# 8_Outputs_Card_with_I2C.net
KiCad netlist of a schematic drawn in EasyEDA
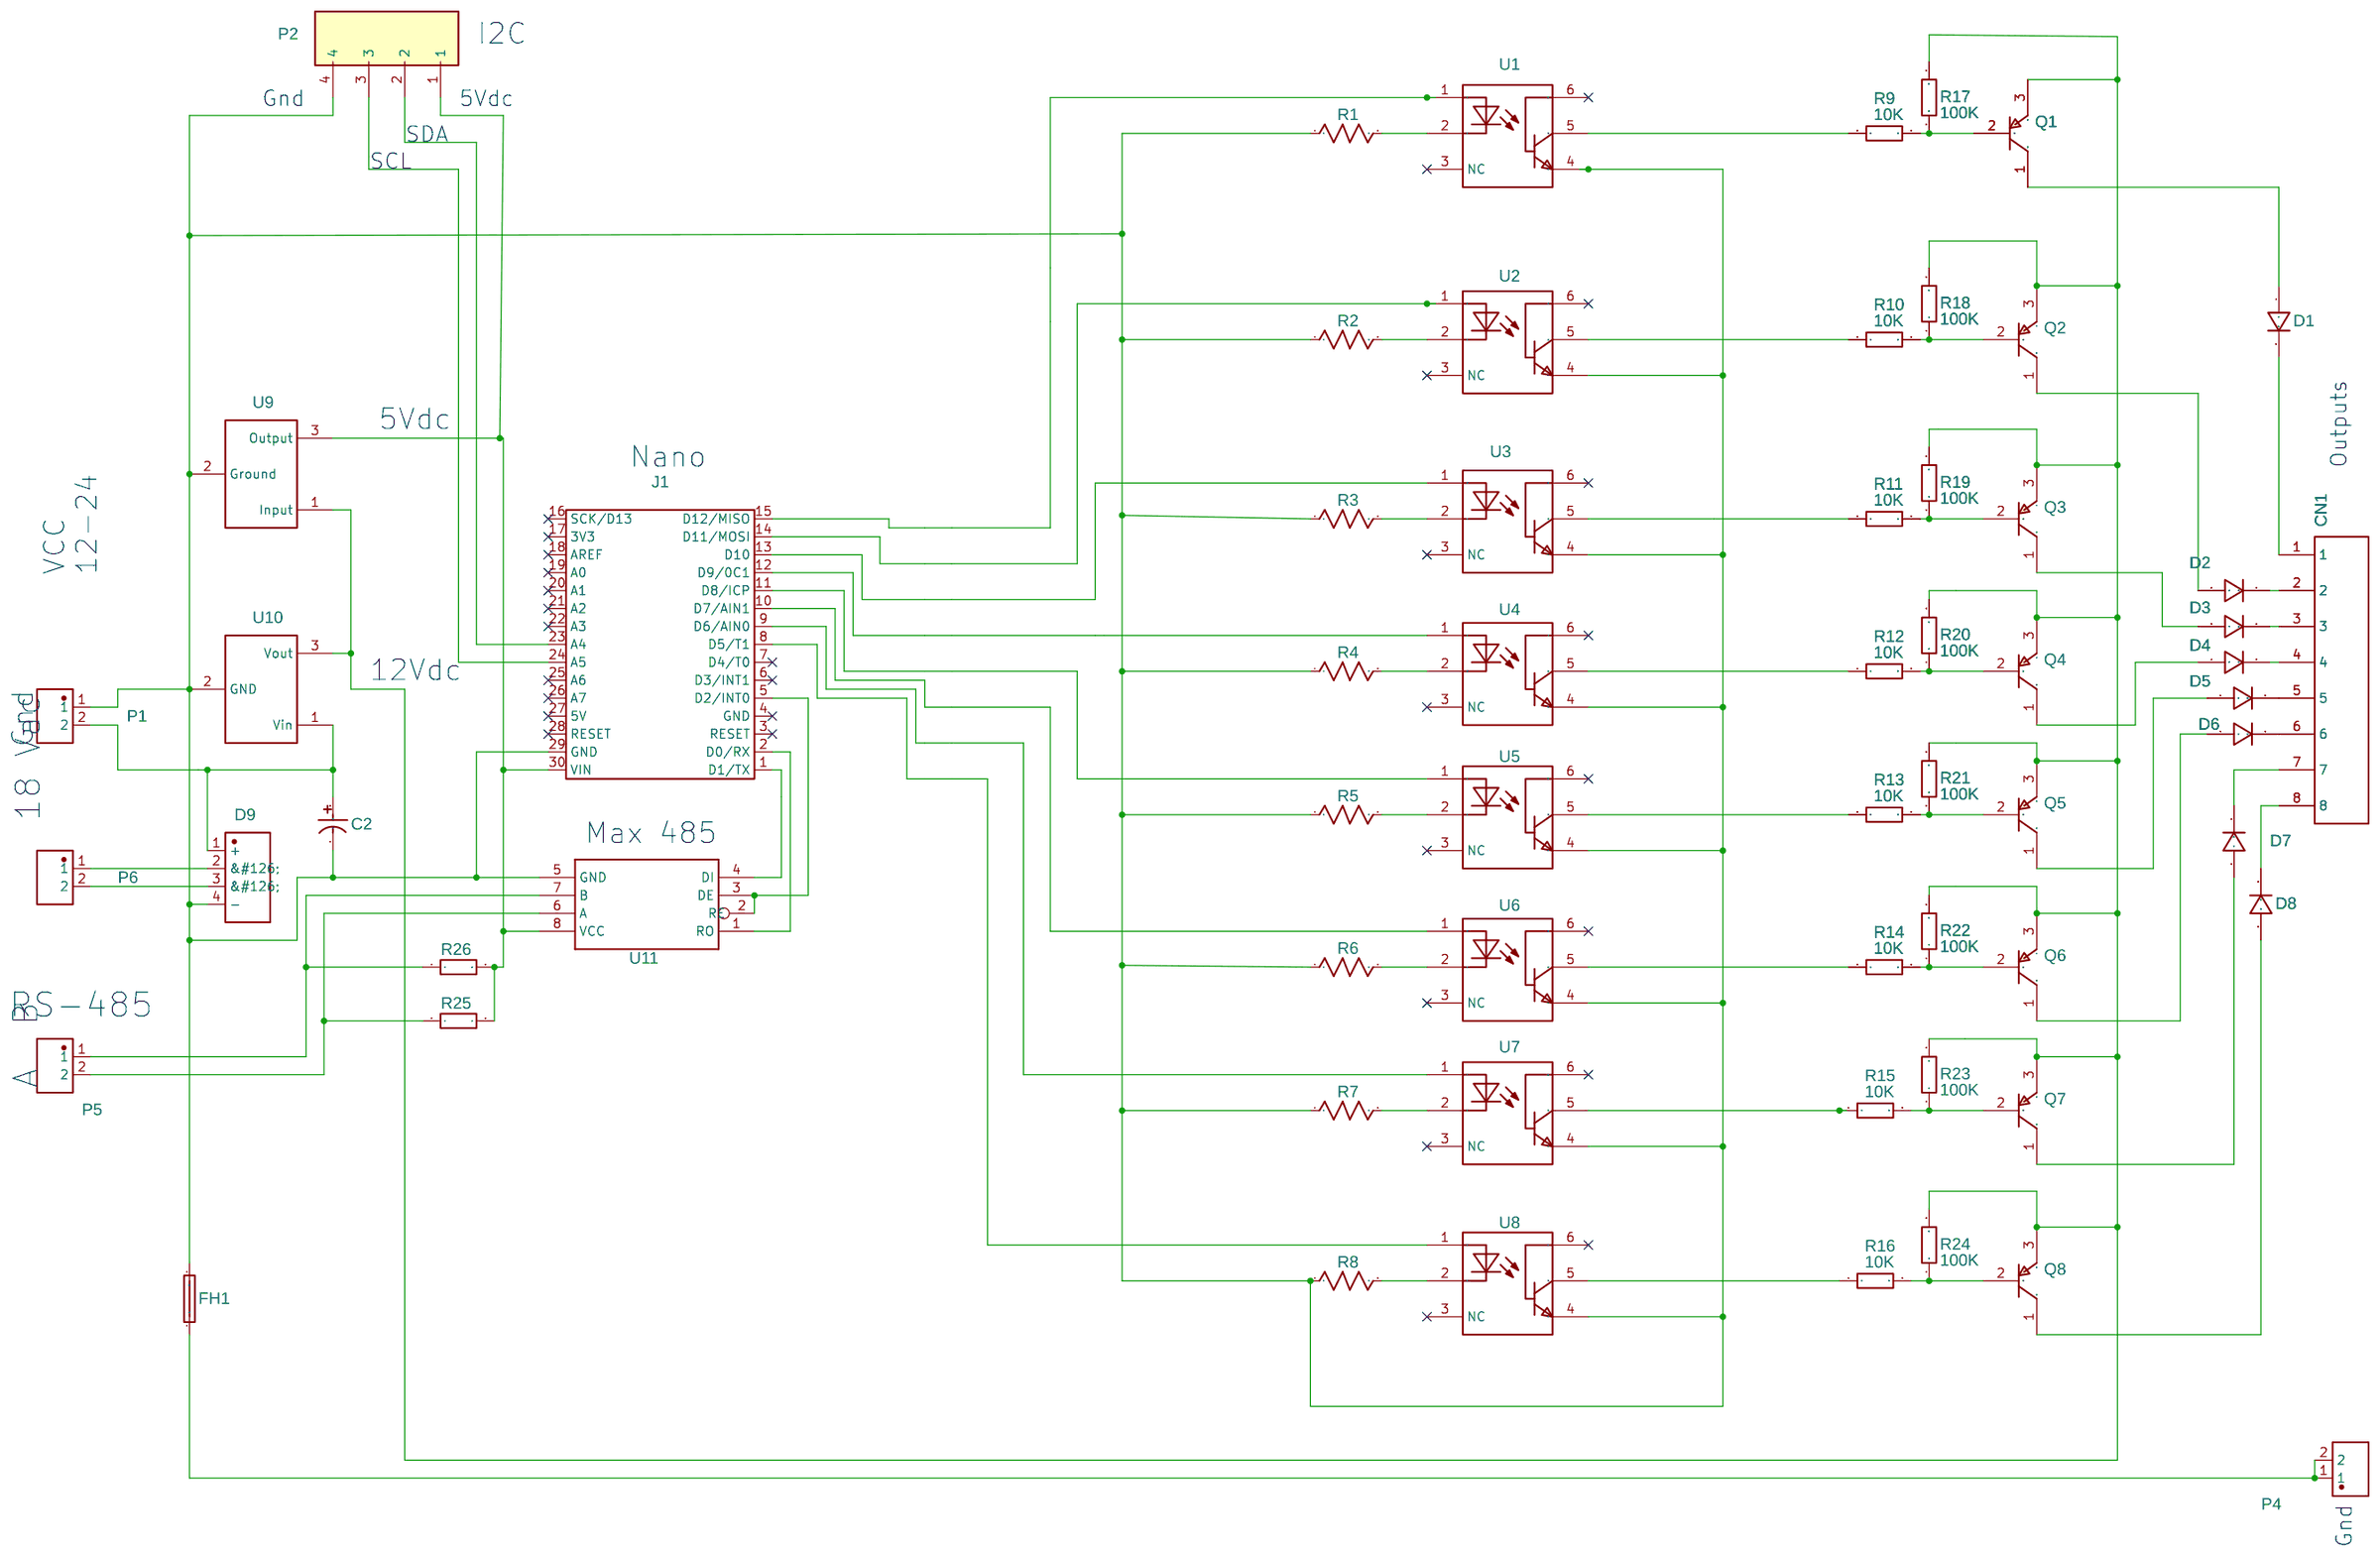
[diagram p0: schematic sheet]

(export (version "E")
  (design (tool "Eeschema 10.0.6"))
  (components
    (comp (ref "C2")
      (value "470uF")
      (fields
        (field (name "BOM_Manufacturer Part") "470uF 100V 16*25")
        (field (name "BOM_Supplier Part") "C72551")
      )
      (libsource (lib "") (part "470uF 100V 16*25"))
    )
    (comp (ref "CN1")
      (value "WJ25C-B-7.62-8P-13-00A")
      (fields (field (name "BOM_Supplier Part") "C49492"))
      (libsource (lib "") (part "Unknown_1530_395"))
    )
    (comp (ref "D1")
      (value "1N4001")
      (fields (field (name "BOM_Supplier Part") "C169150"))
      (libsource (lib "") (part "Unknown_1510_195"))
    )
    (comp (ref "D2")
      (value "1N4001")
      (fields (field (name "BOM_Supplier Part") "C169150"))
      (libsource (lib "") (part "Unknown_1485_345"))
    )
    (comp (ref "D3")
      (value "1N4001")
      (fields (field (name "BOM_Supplier Part") "C169150"))
      (libsource (lib "") (part "Unknown_1485_365"))
    )
    (comp (ref "D4")
      (value "1N4001")
      (fields (field (name "BOM_Supplier Part") "C169150"))
      (libsource (lib "") (part "Unknown_1485_385"))
    )
    (comp (ref "D5")
      (value "1N4001")
      (fields (field (name "BOM_Supplier Part") "C169150"))
      (libsource (lib "") (part "Unknown_1490_405"))
    )
    (comp (ref "D6")
      (value "1N4001")
      (fields (field (name "BOM_Supplier Part") "C169150"))
      (libsource (lib "") (part "Unknown_1490_425"))
    )
    (comp (ref "D7")
      (value "1N4001")
      (fields (field (name "BOM_Supplier Part") "C169150"))
      (libsource (lib "") (part "Unknown_1485_485"))
    )
    (comp (ref "D8")
      (value "1N4001")
      (fields (field (name "BOM_Supplier Part") "C169150"))
      (libsource (lib "") (part "Unknown_1500_520"))
    )
    (comp (ref "D9")
      (value "D50SB100")
      (fields (field (name "BOM_Supplier Part") "C411148"))
      (libsource (lib "") (part "Unknown_370_505"))
    )
    (comp (ref "FH1")
      (value "64600001003")
      (fields (field (name "BOM_Supplier Part") "C206887"))
      (libsource (lib "") (part "Unknown_345_740"))
    )
    (comp (ref "J1") (value "Arduino_Nano_Header") (libsource (lib "") (part "Unknown_605_375")))
    (comp (ref "P1")
      (value "WJ25C-B-2P")
      (fields (field (name "BOM_Supplier Part") "C8422"))
      (libsource (lib "") (part "Unknown_270_415"))
    )
    (comp (ref "P2")
      (value "WJ25C-B-4P")
      (fields (field (name "BOM_Supplier Part") "C8424"))
      (libsource (lib "") (part "WJ25C-B-4P"))
    )
    (comp (ref "P4")
      (value "WJ25C-B-2P")
      (fields (field (name "BOM_Supplier Part") "C8422"))
      (libsource (lib "") (part "Unknown_1550_835"))
    )
    (comp (ref "P5")
      (value "WJ25C-B-2P")
      (fields (field (name "BOM_Supplier Part") "C8422"))
      (libsource (lib "") (part "Unknown_270_610"))
    )
    (comp (ref "P6")
      (value "WJ25C-B-2P")
      (fields (field (name "BOM_Supplier Part") "C8422"))
      (libsource (lib "") (part "Unknown_270_505"))
    )
    (comp (ref "Q1")
      (value "2N4033")
      (fields (field (name "BOM_Supplier Part") "610-2N4033"))
      (libsource (lib "") (part "Unknown_1355_90"))
    )
    (comp (ref "Q2")
      (value "2N4033")
      (fields (field (name "BOM_Supplier Part") "610-2N4033"))
      (libsource (lib "") (part "Unknown_1360_205"))
    )
    (comp (ref "Q3")
      (value "2N4033")
      (fields (field (name "BOM_Supplier Part") "610-2N4033"))
      (libsource (lib "") (part "Unknown_1360_305"))
    )
    (comp (ref "Q4")
      (value "2N4033")
      (fields (field (name "BOM_Supplier Part") "610-2N4033"))
      (libsource (lib "") (part "Unknown_1360_390"))
    )
    (comp (ref "Q5")
      (value "2N4033")
      (fields (field (name "BOM_Supplier Part") "610-2N4033"))
      (libsource (lib "") (part "Unknown_1360_470"))
    )
    (comp (ref "Q6")
      (value "2N4033")
      (fields (field (name "BOM_Supplier Part") "610-2N4033"))
      (libsource (lib "") (part "Unknown_1360_555"))
    )
    (comp (ref "Q7")
      (value "2N4033")
      (fields (field (name "BOM_Supplier Part") "610-2N4033"))
      (libsource (lib "") (part "Unknown_1360_635"))
    )
    (comp (ref "Q8")
      (value "2N4033")
      (fields (field (name "BOM_Supplier Part") "610-2N4033"))
      (libsource (lib "") (part "Unknown_1360_730"))
    )
    (comp (ref "R1")
      (value "1k")
      (fields
        (field (name "BOM_Manufacturer Part") "MFR0W4F1001A50")
        (field (name "BOM_Supplier Part") "C57435")
      )
      (libsource (lib "") (part "Res_AXIAL-0.3(1/8W)_US"))
    )
    (comp (ref "R2")
      (value "1k")
      (fields
        (field (name "BOM_Manufacturer Part") "MFR0W4F1001A50")
        (field (name "BOM_Supplier Part") "C57435")
      )
      (libsource (lib "") (part "Res_AXIAL-0.3(1/8W)_US"))
    )
    (comp (ref "R3")
      (value "1k")
      (fields
        (field (name "BOM_Manufacturer Part") "MFR0W4F1001A50")
        (field (name "BOM_Supplier Part") "C57435")
      )
      (libsource (lib "") (part "Res_AXIAL-0.3(1/8W)_US"))
    )
    (comp (ref "R4")
      (value "1k")
      (fields
        (field (name "BOM_Manufacturer Part") "MFR0W4F1001A50")
        (field (name "BOM_Supplier Part") "C57435")
      )
      (libsource (lib "") (part "Res_AXIAL-0.3(1/8W)_US"))
    )
    (comp (ref "R5")
      (value "1k")
      (fields
        (field (name "BOM_Manufacturer Part") "MFR0W4F1001A50")
        (field (name "BOM_Supplier Part") "C57435")
      )
      (libsource (lib "") (part "Res_AXIAL-0.3(1/8W)_US"))
    )
    (comp (ref "R6")
      (value "1k")
      (fields
        (field (name "BOM_Manufacturer Part") "MFR0W4F1001A50")
        (field (name "BOM_Supplier Part") "C57435")
      )
      (libsource (lib "") (part "Res_AXIAL-0.3(1/8W)_US"))
    )
    (comp (ref "R7")
      (value "1k")
      (fields
        (field (name "BOM_Manufacturer Part") "MFR0W4F1001A50")
        (field (name "BOM_Supplier Part") "C57435")
      )
      (libsource (lib "") (part "Res_AXIAL-0.3(1/8W)_US"))
    )
    (comp (ref "R8")
      (value "1k")
      (fields
        (field (name "BOM_Manufacturer Part") "MFR0W4F1001A50")
        (field (name "BOM_Supplier Part") "C57435")
      )
      (libsource (lib "") (part "Res_AXIAL-0.3(1/8W)_US"))
    )
    (comp (ref "R9")
      (value "10K")
      (fields
        (field (name "BOM_Manufacturer Part") "CFR0W4J0103A50")
        (field (name "BOM_Supplier Part") "C61299")
      )
      (libsource (lib "") (part "CFR0W4J0103A50"))
    )
    (comp (ref "R10")
      (value "10K")
      (fields
        (field (name "BOM_Manufacturer Part") "CFR0W4J0103A50")
        (field (name "BOM_Supplier Part") "C61299")
      )
      (libsource (lib "") (part "CFR0W4J0103A50"))
    )
    (comp (ref "R11")
      (value "10K")
      (fields
        (field (name "BOM_Manufacturer Part") "CFR0W4J0103A50")
        (field (name "BOM_Supplier Part") "C61299")
      )
      (libsource (lib "") (part "CFR0W4J0103A50"))
    )
    (comp (ref "R12")
      (value "10K")
      (fields
        (field (name "BOM_Manufacturer Part") "CFR0W4J0103A50")
        (field (name "BOM_Supplier Part") "C61299")
      )
      (libsource (lib "") (part "CFR0W4J0103A50"))
    )
    (comp (ref "R13")
      (value "10K")
      (fields
        (field (name "BOM_Manufacturer Part") "CFR0W4J0103A50")
        (field (name "BOM_Supplier Part") "C61299")
      )
      (libsource (lib "") (part "CFR0W4J0103A50"))
    )
    (comp (ref "R14")
      (value "10K")
      (fields
        (field (name "BOM_Manufacturer Part") "CFR0W4J0103A50")
        (field (name "BOM_Supplier Part") "C61299")
      )
      (libsource (lib "") (part "CFR0W4J0103A50"))
    )
    (comp (ref "R15")
      (value "10K")
      (fields
        (field (name "BOM_Manufacturer Part") "CFR0W4J0103A50")
        (field (name "BOM_Supplier Part") "C61299")
      )
      (libsource (lib "") (part "CFR0W4J0103A50"))
    )
    (comp (ref "R16")
      (value "10K")
      (fields
        (field (name "BOM_Manufacturer Part") "CFR0W4J0103A50")
        (field (name "BOM_Supplier Part") "C61299")
      )
      (libsource (lib "") (part "CFR0W4J0103A50"))
    )
    (comp (ref "R17")
      (value "100K")
      (fields
        (field (name "BOM_Manufacturer Part") "CFR0W4J0104A50")
        (field (name "BOM_Supplier Part") "C61303")
      )
      (libsource (lib "") (part "CFR0W4J0104A50"))
    )
    (comp (ref "R18")
      (value "100K")
      (fields
        (field (name "BOM_Manufacturer Part") "CFR0W4J0104A50")
        (field (name "BOM_Supplier Part") "C61303")
      )
      (libsource (lib "") (part "CFR0W4J0104A50"))
    )
    (comp (ref "R19")
      (value "100K")
      (fields
        (field (name "BOM_Manufacturer Part") "CFR0W4J0104A50")
        (field (name "BOM_Supplier Part") "C61303")
      )
      (libsource (lib "") (part "CFR0W4J0104A50"))
    )
    (comp (ref "R20")
      (value "100K")
      (fields
        (field (name "BOM_Manufacturer Part") "CFR0W4J0104A50")
        (field (name "BOM_Supplier Part") "C61303")
      )
      (libsource (lib "") (part "CFR0W4J0104A50"))
    )
    (comp (ref "R21")
      (value "100K")
      (fields
        (field (name "BOM_Manufacturer Part") "CFR0W4J0104A50")
        (field (name "BOM_Supplier Part") "C61303")
      )
      (libsource (lib "") (part "CFR0W4J0104A50"))
    )
    (comp (ref "R22")
      (value "100K")
      (fields
        (field (name "BOM_Manufacturer Part") "CFR0W4J0104A50")
        (field (name "BOM_Supplier Part") "C61303")
      )
      (libsource (lib "") (part "CFR0W4J0104A50"))
    )
    (comp (ref "R23")
      (value "100K")
      (fields
        (field (name "BOM_Manufacturer Part") "CFR0W4J0104A50")
        (field (name "BOM_Supplier Part") "C61303")
      )
      (libsource (lib "") (part "CFR0W4J0104A50"))
    )
    (comp (ref "R24")
      (value "100K")
      (fields
        (field (name "BOM_Manufacturer Part") "CFR0W4J0104A50")
        (field (name "BOM_Supplier Part") "C61303")
      )
      (libsource (lib "") (part "CFR0W4J0104A50"))
    )
    (comp (ref "R25")
      (value "10K")
      (fields
        (field (name "BOM_Manufacturer Part") "CFR0W4J0103A50")
        (field (name "BOM_Supplier Part") "C61299")
      )
      (libsource (lib "") (part "CFR0W4J0103A50"))
    )
    (comp (ref "R26")
      (value "10K")
      (fields
        (field (name "BOM_Manufacturer Part") "CFR0W4J0103A50")
        (field (name "BOM_Supplier Part") "C61299")
      )
      (libsource (lib "") (part "CFR0W4J0103A50"))
    )
    (comp (ref "U1")
      (value "4N25M")
      (fields (field (name "BOM_Supplier Part") "C5241"))
      (libsource (lib "") (part "Unknown_1080_90"))
    )
    (comp (ref "U2")
      (value "4N25M")
      (fields (field (name "BOM_Supplier Part") "C5241"))
      (libsource (lib "") (part "Unknown_1080_205"))
    )
    (comp (ref "U3")
      (value "4N25M")
      (fields (field (name "BOM_Supplier Part") "C5241"))
      (libsource (lib "") (part "Unknown_1080_305"))
    )
    (comp (ref "U4")
      (value "4N25M")
      (fields (field (name "BOM_Supplier Part") "C5241"))
      (libsource (lib "") (part "Unknown_1080_390"))
    )
    (comp (ref "U5")
      (value "4N25M")
      (fields (field (name "BOM_Supplier Part") "C5241"))
      (libsource (lib "") (part "Unknown_1080_470"))
    )
    (comp (ref "U6")
      (value "4N25M")
      (fields (field (name "BOM_Supplier Part") "C5241"))
      (libsource (lib "") (part "Unknown_1080_555"))
    )
    (comp (ref "U7")
      (value "4N25M")
      (fields (field (name "BOM_Supplier Part") "C5241"))
      (libsource (lib "") (part "Unknown_1080_635"))
    )
    (comp (ref "U8")
      (value "4N25M")
      (fields (field (name "BOM_Supplier Part") "C5241"))
      (libsource (lib "") (part "Unknown_1080_730"))
    )
    (comp (ref "U9")
      (value "MC7805BTG")
      (fields (field (name "BOM_Supplier Part") "C45385"))
      (libsource (lib "") (part "Unknown_385_280"))
    )
    (comp (ref "U10")
      (value "CJ7812")
      (fields (field (name "BOM_Supplier Part") "C77894"))
      (libsource (lib "") (part "Unknown_385_400"))
    )
    (comp (ref "U11") (value "MAX485DIL") (libsource (lib "") (part "Unknown_600_520")))
  )
  (nets
    (net (code "1") (name "Net-(CN1-Pad1)") (class "Default")
      (node (ref "CN1") (pin "1") (pinfunction "1_1") (pintype "input"))
      (node (ref "D1") (pin "2") (pinfunction "2_2") (pintype "unspecified"))
    )
    (net (code "2") (name "Net-(CN1-Pad2)") (class "Default")
      (node (ref "CN1") (pin "2") (pinfunction "2_2") (pintype "input"))
      (node (ref "D2") (pin "2") (pinfunction "2_2") (pintype "unspecified"))
    )
    (net (code "3") (name "Net-(CN1-Pad3)") (class "Default")
      (node (ref "CN1") (pin "3") (pinfunction "3_3") (pintype "input"))
      (node (ref "D3") (pin "2") (pinfunction "2_2") (pintype "unspecified"))
    )
    (net (code "4") (name "Net-(CN1-Pad4)") (class "Default")
      (node (ref "CN1") (pin "4") (pinfunction "4_4") (pintype "input"))
      (node (ref "D4") (pin "2") (pinfunction "2_2") (pintype "unspecified"))
    )
    (net (code "5") (name "Net-(CN1-Pad5)") (class "Default")
      (node (ref "CN1") (pin "5") (pinfunction "5_5") (pintype "input"))
      (node (ref "D5") (pin "2") (pinfunction "2_2") (pintype "unspecified"))
    )
    (net (code "6") (name "Net-(CN1-Pad6)") (class "Default")
      (node (ref "CN1") (pin "6") (pinfunction "6_6") (pintype "input"))
      (node (ref "D6") (pin "2") (pinfunction "2_2") (pintype "unspecified"))
    )
    (net (code "7") (name "Net-(CN1-Pad7)") (class "Default")
      (node (ref "CN1") (pin "7") (pinfunction "7_7") (pintype "input"))
      (node (ref "D7") (pin "2") (pinfunction "2_2") (pintype "unspecified"))
    )
    (net (code "8") (name "Net-(CN1-Pad8)") (class "Default")
      (node (ref "CN1") (pin "8") (pinfunction "8_8") (pintype "input"))
      (node (ref "D8") (pin "2") (pinfunction "2_2") (pintype "unspecified"))
    )
    (net (code "9") (name "Net-(D9-&#126;-Pad2)") (class "Default")
      (node (ref "D9") (pin "2") (pinfunction "&#126;_2") (pintype "unspecified"))
      (node (ref "P6") (pin "1") (pinfunction "1_1") (pintype "unspecified"))
    )
    (net (code "10") (name "Net-(D9-&#126;-Pad3)") (class "Default")
      (node (ref "D9") (pin "3") (pinfunction "&#126;_3") (pintype "unspecified"))
      (node (ref "P6") (pin "2") (pinfunction "2_2") (pintype "unspecified"))
    )
    (net (code "11") (name "Net-(D9-+)") (class "Default")
      (node (ref "C2") (pin "1") (pinfunction "1_1") (pintype "input"))
      (node (ref "D9") (pin "1") (pinfunction "+_1") (pintype "unspecified"))
      (node (ref "P1") (pin "2") (pinfunction "2_2") (pintype "unspecified"))
      (node (ref "U10") (pin "1") (pinfunction "Vin_1") (pintype "unspecified"))
    )
    (net (code "12") (name "Net-(D9--)") (class "Default")
      (node (ref "C2") (pin "2") (pinfunction "2_2") (pintype "input"))
      (node (ref "D9") (pin "4") (pinfunction "-_4") (pintype "unspecified"))
      (node (ref "FH1") (pin "2") (pinfunction "2_2") (pintype "unspecified"))
      (node (ref "J1") (pin "29") (pinfunction "GND_29") (pintype "unspecified"))
      (node (ref "P1") (pin "1") (pinfunction "1_1") (pintype "unspecified"))
      (node (ref "P2") (pin "4") (pinfunction "4_4") (pintype "input"))
      (node (ref "R1") (pin "1") (pinfunction "1_1") (pintype "unspecified"))
      (node (ref "R2") (pin "1") (pinfunction "1_1") (pintype "unspecified"))
      (node (ref "R3") (pin "1") (pinfunction "1_1") (pintype "unspecified"))
      (node (ref "R4") (pin "1") (pinfunction "1_1") (pintype "unspecified"))
      (node (ref "R5") (pin "1") (pinfunction "1_1") (pintype "unspecified"))
      (node (ref "R6") (pin "1") (pinfunction "1_1") (pintype "unspecified"))
      (node (ref "R7") (pin "1") (pinfunction "1_1") (pintype "unspecified"))
      (node (ref "R8") (pin "1") (pinfunction "1_1") (pintype "unspecified"))
      (node (ref "U1") (pin "4") (pinfunction "4_4") (pintype "unspecified"))
      (node (ref "U10") (pin "2") (pinfunction "GND_2") (pintype "unspecified"))
      (node (ref "U11") (pin "5") (pinfunction "GND_5") (pintype "unspecified"))
      (node (ref "U2") (pin "4") (pinfunction "4_4") (pintype "unspecified"))
      (node (ref "U3") (pin "4") (pinfunction "4_4") (pintype "unspecified"))
      (node (ref "U4") (pin "4") (pinfunction "4_4") (pintype "unspecified"))
      (node (ref "U5") (pin "4") (pinfunction "4_4") (pintype "unspecified"))
      (node (ref "U6") (pin "4") (pinfunction "4_4") (pintype "unspecified"))
      (node (ref "U7") (pin "4") (pinfunction "4_4") (pintype "unspecified"))
      (node (ref "U8") (pin "4") (pinfunction "4_4") (pintype "unspecified"))
      (node (ref "U9") (pin "2") (pinfunction "Ground_2") (pintype "unspecified"))
    )
    (net (code "13") (name "Net-(FH1-Pad1)") (class "Default")
      (node (ref "FH1") (pin "1") (pinfunction "1_1") (pintype "unspecified"))
      (node (ref "P4") (pin "1") (pinfunction "1_1") (pintype "unspecified"))
      (node (ref "P4") (pin "2") (pinfunction "2_2") (pintype "unspecified"))
    )
    (net (code "14") (name "Net-(J1-A4)") (class "Default")
      (node (ref "J1") (pin "23") (pinfunction "A4_23") (pintype "unspecified"))
      (node (ref "P2") (pin "2") (pinfunction "2_2") (pintype "input"))
    )
    (net (code "15") (name "Net-(J1-A5)") (class "Default")
      (node (ref "J1") (pin "24") (pinfunction "A5_24") (pintype "unspecified"))
      (node (ref "P2") (pin "3") (pinfunction "3_3") (pintype "input"))
    )
    (net (code "16") (name "Net-(J1-D0{slash}RX)") (class "Default")
      (node (ref "J1") (pin "2") (pinfunction "D0/RX_2") (pintype "unspecified"))
      (node (ref "U11") (pin "1") (pinfunction "RO_1") (pintype "unspecified"))
    )
    (net (code "17") (name "Net-(J1-D1{slash}TX)") (class "Default")
      (node (ref "J1") (pin "1") (pinfunction "D1/TX_1") (pintype "unspecified"))
      (node (ref "U11") (pin "4") (pinfunction "DI_4") (pintype "unspecified"))
    )
    (net (code "18") (name "Net-(J1-D2{slash}INT0)") (class "Default")
      (node (ref "J1") (pin "5") (pinfunction "D2/INT0_5") (pintype "unspecified"))
      (node (ref "U11") (pin "2") (pinfunction "RE_2") (pintype "unspecified"))
      (node (ref "U11") (pin "3") (pinfunction "DE_3") (pintype "unspecified"))
    )
    (net (code "19") (name "Net-(J1-D5{slash}T1)") (class "Default")
      (node (ref "J1") (pin "8") (pinfunction "D5/T1_8") (pintype "unspecified"))
      (node (ref "U8") (pin "1") (pinfunction "1_1") (pintype "unspecified"))
    )
    (net (code "20") (name "Net-(J1-D6{slash}AIN0)") (class "Default")
      (node (ref "J1") (pin "9") (pinfunction "D6/AIN0_9") (pintype "unspecified"))
      (node (ref "U7") (pin "1") (pinfunction "1_1") (pintype "unspecified"))
    )
    (net (code "21") (name "Net-(J1-D7{slash}AIN1)") (class "Default")
      (node (ref "J1") (pin "10") (pinfunction "D7/AIN1_10") (pintype "unspecified"))
      (node (ref "U6") (pin "1") (pinfunction "1_1") (pintype "unspecified"))
    )
    (net (code "22") (name "Net-(J1-D8{slash}ICP)") (class "Default")
      (node (ref "J1") (pin "11") (pinfunction "D8/ICP_11") (pintype "unspecified"))
      (node (ref "U5") (pin "1") (pinfunction "1_1") (pintype "unspecified"))
    )
    (net (code "23") (name "Net-(J1-D9{slash}0C1)") (class "Default")
      (node (ref "J1") (pin "12") (pinfunction "D9/0C1_12") (pintype "unspecified"))
      (node (ref "U4") (pin "1") (pinfunction "1_1") (pintype "unspecified"))
    )
    (net (code "24") (name "Net-(J1-D10)") (class "Default")
      (node (ref "J1") (pin "13") (pinfunction "D10_13") (pintype "unspecified"))
      (node (ref "U3") (pin "1") (pinfunction "1_1") (pintype "unspecified"))
    )
    (net (code "25") (name "Net-(J1-D11{slash}MOSI)") (class "Default")
      (node (ref "J1") (pin "14") (pinfunction "D11/MOSI_14") (pintype "unspecified"))
      (node (ref "U2") (pin "1") (pinfunction "1_1") (pintype "unspecified"))
    )
    (net (code "26") (name "Net-(J1-D12{slash}MISO)") (class "Default")
      (node (ref "J1") (pin "15") (pinfunction "D12/MISO_15") (pintype "unspecified"))
      (node (ref "U1") (pin "1") (pinfunction "1_1") (pintype "unspecified"))
    )
    (net (code "27") (name "Net-(J1-VIN)") (class "Default")
      (node (ref "J1") (pin "30") (pinfunction "VIN_30") (pintype "unspecified"))
      (node (ref "P2") (pin "1") (pinfunction "1_1") (pintype "input"))
      (node (ref "R25") (pin "2") (pinfunction "2_2") (pintype "input"))
      (node (ref "R26") (pin "2") (pinfunction "2_2") (pintype "input"))
      (node (ref "U11") (pin "8") (pinfunction "VCC_8") (pintype "unspecified"))
      (node (ref "U9") (pin "3") (pinfunction "Output_3") (pintype "unspecified"))
    )
    (net (code "28") (name "Net-(Q1-B)") (class "Default")
      (node (ref "Q1") (pin "2") (pinfunction "B_2") (pintype "unspecified"))
      (node (ref "R17") (pin "1") (pinfunction "1_1") (pintype "input"))
      (node (ref "R9") (pin "2") (pinfunction "2_2") (pintype "input"))
    )
    (net (code "29") (name "Net-(Q1-C)") (class "Default")
      (node (ref "D1") (pin "1") (pinfunction "1_1") (pintype "unspecified"))
      (node (ref "Q1") (pin "1") (pinfunction "C_1") (pintype "unspecified"))
    )
    (net (code "30") (name "Net-(Q1-E)") (class "Default")
      (node (ref "Q1") (pin "3") (pinfunction "E_3") (pintype "unspecified"))
      (node (ref "Q2") (pin "3") (pinfunction "E_3") (pintype "unspecified"))
      (node (ref "Q3") (pin "3") (pinfunction "E_3") (pintype "unspecified"))
      (node (ref "Q4") (pin "3") (pinfunction "E_3") (pintype "unspecified"))
      (node (ref "Q5") (pin "3") (pinfunction "E_3") (pintype "unspecified"))
      (node (ref "Q6") (pin "3") (pinfunction "E_3") (pintype "unspecified"))
      (node (ref "Q7") (pin "3") (pinfunction "E_3") (pintype "unspecified"))
      (node (ref "Q8") (pin "3") (pinfunction "E_3") (pintype "unspecified"))
      (node (ref "R17") (pin "2") (pinfunction "2_2") (pintype "input"))
      (node (ref "R18") (pin "2") (pinfunction "2_2") (pintype "input"))
      (node (ref "R19") (pin "2") (pinfunction "2_2") (pintype "input"))
      (node (ref "R20") (pin "2") (pinfunction "2_2") (pintype "input"))
      (node (ref "R21") (pin "2") (pinfunction "2_2") (pintype "input"))
      (node (ref "R22") (pin "2") (pinfunction "2_2") (pintype "input"))
      (node (ref "R23") (pin "2") (pinfunction "2_2") (pintype "input"))
      (node (ref "R24") (pin "2") (pinfunction "2_2") (pintype "input"))
      (node (ref "U10") (pin "3") (pinfunction "Vout_3") (pintype "unspecified"))
      (node (ref "U9") (pin "1") (pinfunction "Input_1") (pintype "unspecified"))
    )
    (net (code "31") (name "Net-(Q2-B)") (class "Default")
      (node (ref "Q2") (pin "2") (pinfunction "B_2") (pintype "unspecified"))
      (node (ref "R10") (pin "2") (pinfunction "2_2") (pintype "input"))
      (node (ref "R18") (pin "1") (pinfunction "1_1") (pintype "input"))
    )
    (net (code "32") (name "Net-(Q2-C)") (class "Default")
      (node (ref "D2") (pin "1") (pinfunction "1_1") (pintype "unspecified"))
      (node (ref "Q2") (pin "1") (pinfunction "C_1") (pintype "unspecified"))
    )
    (net (code "33") (name "Net-(Q3-B)") (class "Default")
      (node (ref "Q3") (pin "2") (pinfunction "B_2") (pintype "unspecified"))
      (node (ref "R11") (pin "2") (pinfunction "2_2") (pintype "input"))
      (node (ref "R19") (pin "1") (pinfunction "1_1") (pintype "input"))
    )
    (net (code "34") (name "Net-(Q3-C)") (class "Default")
      (node (ref "D3") (pin "1") (pinfunction "1_1") (pintype "unspecified"))
      (node (ref "Q3") (pin "1") (pinfunction "C_1") (pintype "unspecified"))
    )
    (net (code "35") (name "Net-(Q4-B)") (class "Default")
      (node (ref "Q4") (pin "2") (pinfunction "B_2") (pintype "unspecified"))
      (node (ref "R12") (pin "2") (pinfunction "2_2") (pintype "input"))
      (node (ref "R20") (pin "1") (pinfunction "1_1") (pintype "input"))
    )
    (net (code "36") (name "Net-(Q4-C)") (class "Default")
      (node (ref "D4") (pin "1") (pinfunction "1_1") (pintype "unspecified"))
      (node (ref "Q4") (pin "1") (pinfunction "C_1") (pintype "unspecified"))
    )
    (net (code "37") (name "Net-(Q5-B)") (class "Default")
      (node (ref "Q5") (pin "2") (pinfunction "B_2") (pintype "unspecified"))
      (node (ref "R13") (pin "2") (pinfunction "2_2") (pintype "input"))
      (node (ref "R21") (pin "1") (pinfunction "1_1") (pintype "input"))
    )
    (net (code "38") (name "Net-(Q5-C)") (class "Default")
      (node (ref "D5") (pin "1") (pinfunction "1_1") (pintype "unspecified"))
      (node (ref "Q5") (pin "1") (pinfunction "C_1") (pintype "unspecified"))
    )
    (net (code "39") (name "Net-(Q6-B)") (class "Default")
      (node (ref "Q6") (pin "2") (pinfunction "B_2") (pintype "unspecified"))
      (node (ref "R14") (pin "2") (pinfunction "2_2") (pintype "input"))
      (node (ref "R22") (pin "1") (pinfunction "1_1") (pintype "input"))
    )
    (net (code "40") (name "Net-(Q6-C)") (class "Default")
      (node (ref "D6") (pin "1") (pinfunction "1_1") (pintype "unspecified"))
      (node (ref "Q6") (pin "1") (pinfunction "C_1") (pintype "unspecified"))
    )
    (net (code "41") (name "Net-(Q7-B)") (class "Default")
      (node (ref "Q7") (pin "2") (pinfunction "B_2") (pintype "unspecified"))
      (node (ref "R15") (pin "2") (pinfunction "2_2") (pintype "input"))
      (node (ref "R23") (pin "1") (pinfunction "1_1") (pintype "input"))
    )
    (net (code "42") (name "Net-(Q7-C)") (class "Default")
      (node (ref "D7") (pin "1") (pinfunction "1_1") (pintype "unspecified"))
      (node (ref "Q7") (pin "1") (pinfunction "C_1") (pintype "unspecified"))
    )
    (net (code "43") (name "Net-(Q8-B)") (class "Default")
      (node (ref "Q8") (pin "2") (pinfunction "B_2") (pintype "unspecified"))
      (node (ref "R16") (pin "2") (pinfunction "2_2") (pintype "input"))
      (node (ref "R24") (pin "1") (pinfunction "1_1") (pintype "input"))
    )
    (net (code "44") (name "Net-(Q8-C)") (class "Default")
      (node (ref "D8") (pin "1") (pinfunction "1_1") (pintype "unspecified"))
      (node (ref "Q8") (pin "1") (pinfunction "C_1") (pintype "unspecified"))
    )
    (net (code "45") (name "Net-(R1-Pad2)") (class "Default")
      (node (ref "R1") (pin "2") (pinfunction "2_2") (pintype "unspecified"))
      (node (ref "U1") (pin "2") (pinfunction "2_2") (pintype "unspecified"))
    )
    (net (code "46") (name "Net-(R2-Pad2)") (class "Default")
      (node (ref "R2") (pin "2") (pinfunction "2_2") (pintype "unspecified"))
      (node (ref "U2") (pin "2") (pinfunction "2_2") (pintype "unspecified"))
    )
    (net (code "47") (name "Net-(R3-Pad2)") (class "Default")
      (node (ref "R3") (pin "2") (pinfunction "2_2") (pintype "unspecified"))
      (node (ref "U3") (pin "2") (pinfunction "2_2") (pintype "unspecified"))
    )
    (net (code "48") (name "Net-(R4-Pad2)") (class "Default")
      (node (ref "R4") (pin "2") (pinfunction "2_2") (pintype "unspecified"))
      (node (ref "U4") (pin "2") (pinfunction "2_2") (pintype "unspecified"))
    )
    (net (code "49") (name "Net-(R5-Pad2)") (class "Default")
      (node (ref "R5") (pin "2") (pinfunction "2_2") (pintype "unspecified"))
      (node (ref "U5") (pin "2") (pinfunction "2_2") (pintype "unspecified"))
    )
    (net (code "50") (name "Net-(R6-Pad2)") (class "Default")
      (node (ref "R6") (pin "2") (pinfunction "2_2") (pintype "unspecified"))
      (node (ref "U6") (pin "2") (pinfunction "2_2") (pintype "unspecified"))
    )
    (net (code "51") (name "Net-(R7-Pad2)") (class "Default")
      (node (ref "R7") (pin "2") (pinfunction "2_2") (pintype "unspecified"))
      (node (ref "U7") (pin "2") (pinfunction "2_2") (pintype "unspecified"))
    )
    (net (code "52") (name "Net-(R8-Pad2)") (class "Default")
      (node (ref "R8") (pin "2") (pinfunction "2_2") (pintype "unspecified"))
      (node (ref "U8") (pin "2") (pinfunction "2_2") (pintype "unspecified"))
    )
    (net (code "53") (name "Net-(R9-Pad1)") (class "Default")
      (node (ref "R9") (pin "1") (pinfunction "1_1") (pintype "input"))
      (node (ref "U1") (pin "5") (pinfunction "5_5") (pintype "unspecified"))
    )
    (net (code "54") (name "Net-(R10-Pad1)") (class "Default")
      (node (ref "R10") (pin "1") (pinfunction "1_1") (pintype "input"))
      (node (ref "U2") (pin "5") (pinfunction "5_5") (pintype "unspecified"))
    )
    (net (code "55") (name "Net-(R11-Pad1)") (class "Default")
      (node (ref "R11") (pin "1") (pinfunction "1_1") (pintype "input"))
      (node (ref "U3") (pin "5") (pinfunction "5_5") (pintype "unspecified"))
    )
    (net (code "56") (name "Net-(R12-Pad1)") (class "Default")
      (node (ref "R12") (pin "1") (pinfunction "1_1") (pintype "input"))
      (node (ref "U4") (pin "5") (pinfunction "5_5") (pintype "unspecified"))
    )
    (net (code "57") (name "Net-(R13-Pad1)") (class "Default")
      (node (ref "R13") (pin "1") (pinfunction "1_1") (pintype "input"))
      (node (ref "U5") (pin "5") (pinfunction "5_5") (pintype "unspecified"))
    )
    (net (code "58") (name "Net-(R14-Pad1)") (class "Default")
      (node (ref "R14") (pin "1") (pinfunction "1_1") (pintype "input"))
      (node (ref "U6") (pin "5") (pinfunction "5_5") (pintype "unspecified"))
    )
    (net (code "59") (name "Net-(R15-Pad1)") (class "Default")
      (node (ref "R15") (pin "1") (pinfunction "1_1") (pintype "input"))
      (node (ref "U7") (pin "5") (pinfunction "5_5") (pintype "unspecified"))
    )
    (net (code "60") (name "Net-(R16-Pad1)") (class "Default")
      (node (ref "R16") (pin "1") (pinfunction "1_1") (pintype "input"))
      (node (ref "U8") (pin "5") (pinfunction "5_5") (pintype "unspecified"))
    )
    (net (code "61") (name "Net-(U11-A)") (class "Default")
      (node (ref "P5") (pin "2") (pinfunction "2_2") (pintype "unspecified"))
      (node (ref "R25") (pin "1") (pinfunction "1_1") (pintype "input"))
      (node (ref "U11") (pin "6") (pinfunction "A_6") (pintype "unspecified"))
    )
    (net (code "62") (name "Net-(U11-B)") (class "Default")
      (node (ref "P5") (pin "1") (pinfunction "1_1") (pintype "unspecified"))
      (node (ref "R26") (pin "1") (pinfunction "1_1") (pintype "input"))
      (node (ref "U11") (pin "7") (pinfunction "B_7") (pintype "unspecified"))
    )
    (net (code "63") (name "unconnected-(J1-3V3-Pad17)") (class "Default")
      (node (ref "J1") (pin "17") (pinfunction "3V3_17") (pintype "unspecified+no_connect"))
    )
    (net (code "64") (name "unconnected-(J1-5V-Pad27)") (class "Default")
      (node (ref "J1") (pin "27") (pinfunction "5V_27") (pintype "unspecified+no_connect"))
    )
    (net (code "65") (name "unconnected-(J1-A0-Pad19)") (class "Default")
      (node (ref "J1") (pin "19") (pinfunction "A0_19") (pintype "unspecified+no_connect"))
    )
    (net (code "66") (name "unconnected-(J1-A1-Pad20)") (class "Default")
      (node (ref "J1") (pin "20") (pinfunction "A1_20") (pintype "unspecified+no_connect"))
    )
    (net (code "67") (name "unconnected-(J1-A2-Pad21)") (class "Default")
      (node (ref "J1") (pin "21") (pinfunction "A2_21") (pintype "unspecified+no_connect"))
    )
    (net (code "68") (name "unconnected-(J1-A3-Pad22)") (class "Default")
      (node (ref "J1") (pin "22") (pinfunction "A3_22") (pintype "unspecified+no_connect"))
    )
    (net (code "69") (name "unconnected-(J1-A6-Pad25)") (class "Default")
      (node (ref "J1") (pin "25") (pinfunction "A6_25") (pintype "unspecified+no_connect"))
    )
    (net (code "70") (name "unconnected-(J1-A7-Pad26)") (class "Default")
      (node (ref "J1") (pin "26") (pinfunction "A7_26") (pintype "unspecified+no_connect"))
    )
    (net (code "71") (name "unconnected-(J1-AREF-Pad18)") (class "Default")
      (node (ref "J1") (pin "18") (pinfunction "AREF_18") (pintype "unspecified+no_connect"))
    )
    (net (code "72") (name "unconnected-(J1-D3{slash}INT1-Pad6)") (class "Default")
      (node (ref "J1") (pin "6") (pinfunction "D3/INT1_6") (pintype "unspecified+no_connect"))
    )
    (net (code "73") (name "unconnected-(J1-D4{slash}T0-Pad7)") (class "Default")
      (node (ref "J1") (pin "7") (pinfunction "D4/T0_7") (pintype "unspecified+no_connect"))
    )
    (net (code "74") (name "unconnected-(J1-GND-Pad4)") (class "Default")
      (node (ref "J1") (pin "4") (pinfunction "GND_4") (pintype "unspecified+no_connect"))
    )
    (net (code "75") (name "unconnected-(J1-RESET-Pad3)") (class "Default")
      (node (ref "J1") (pin "3") (pinfunction "RESET_3") (pintype "unspecified+no_connect"))
    )
    (net (code "76") (name "unconnected-(J1-RESET-Pad28)") (class "Default")
      (node (ref "J1") (pin "28") (pinfunction "RESET_28") (pintype "unspecified+no_connect"))
    )
    (net (code "77") (name "unconnected-(J1-SCK{slash}D13-Pad16)") (class "Default")
      (node (ref "J1") (pin "16") (pinfunction "SCK/D13_16") (pintype "unspecified+no_connect"))
    )
    (net (code "78") (name "unconnected-(U1-NC-Pad3)") (class "Default")
      (node (ref "U1") (pin "3") (pinfunction "NC_3") (pintype "unspecified+no_connect"))
    )
    (net (code "79") (name "unconnected-(U1-Pad6)") (class "Default")
      (node (ref "U1") (pin "6") (pinfunction "6_6") (pintype "unspecified+no_connect"))
    )
    (net (code "80") (name "unconnected-(U2-NC-Pad3)") (class "Default")
      (node (ref "U2") (pin "3") (pinfunction "NC_3") (pintype "unspecified+no_connect"))
    )
    (net (code "81") (name "unconnected-(U2-Pad6)") (class "Default")
      (node (ref "U2") (pin "6") (pinfunction "6_6") (pintype "unspecified+no_connect"))
    )
    (net (code "82") (name "unconnected-(U3-NC-Pad3)") (class "Default")
      (node (ref "U3") (pin "3") (pinfunction "NC_3") (pintype "unspecified+no_connect"))
    )
    (net (code "83") (name "unconnected-(U3-Pad6)") (class "Default")
      (node (ref "U3") (pin "6") (pinfunction "6_6") (pintype "unspecified+no_connect"))
    )
    (net (code "84") (name "unconnected-(U4-NC-Pad3)") (class "Default")
      (node (ref "U4") (pin "3") (pinfunction "NC_3") (pintype "unspecified+no_connect"))
    )
    (net (code "85") (name "unconnected-(U4-Pad6)") (class "Default")
      (node (ref "U4") (pin "6") (pinfunction "6_6") (pintype "unspecified+no_connect"))
    )
    (net (code "86") (name "unconnected-(U5-NC-Pad3)") (class "Default")
      (node (ref "U5") (pin "3") (pinfunction "NC_3") (pintype "unspecified+no_connect"))
    )
    (net (code "87") (name "unconnected-(U5-Pad6)") (class "Default")
      (node (ref "U5") (pin "6") (pinfunction "6_6") (pintype "unspecified+no_connect"))
    )
    (net (code "88") (name "unconnected-(U6-NC-Pad3)") (class "Default")
      (node (ref "U6") (pin "3") (pinfunction "NC_3") (pintype "unspecified+no_connect"))
    )
    (net (code "89") (name "unconnected-(U6-Pad6)") (class "Default")
      (node (ref "U6") (pin "6") (pinfunction "6_6") (pintype "unspecified+no_connect"))
    )
    (net (code "90") (name "unconnected-(U7-NC-Pad3)") (class "Default")
      (node (ref "U7") (pin "3") (pinfunction "NC_3") (pintype "unspecified+no_connect"))
    )
    (net (code "91") (name "unconnected-(U7-Pad6)") (class "Default")
      (node (ref "U7") (pin "6") (pinfunction "6_6") (pintype "unspecified+no_connect"))
    )
    (net (code "92") (name "unconnected-(U8-NC-Pad3)") (class "Default")
      (node (ref "U8") (pin "3") (pinfunction "NC_3") (pintype "unspecified+no_connect"))
    )
    (net (code "93") (name "unconnected-(U8-Pad6)") (class "Default")
      (node (ref "U8") (pin "6") (pinfunction "6_6") (pintype "unspecified+no_connect"))
    )
  )
)
